# Oscilloscope.net
KiCad netlist of a schematic drawn in EasyEDA
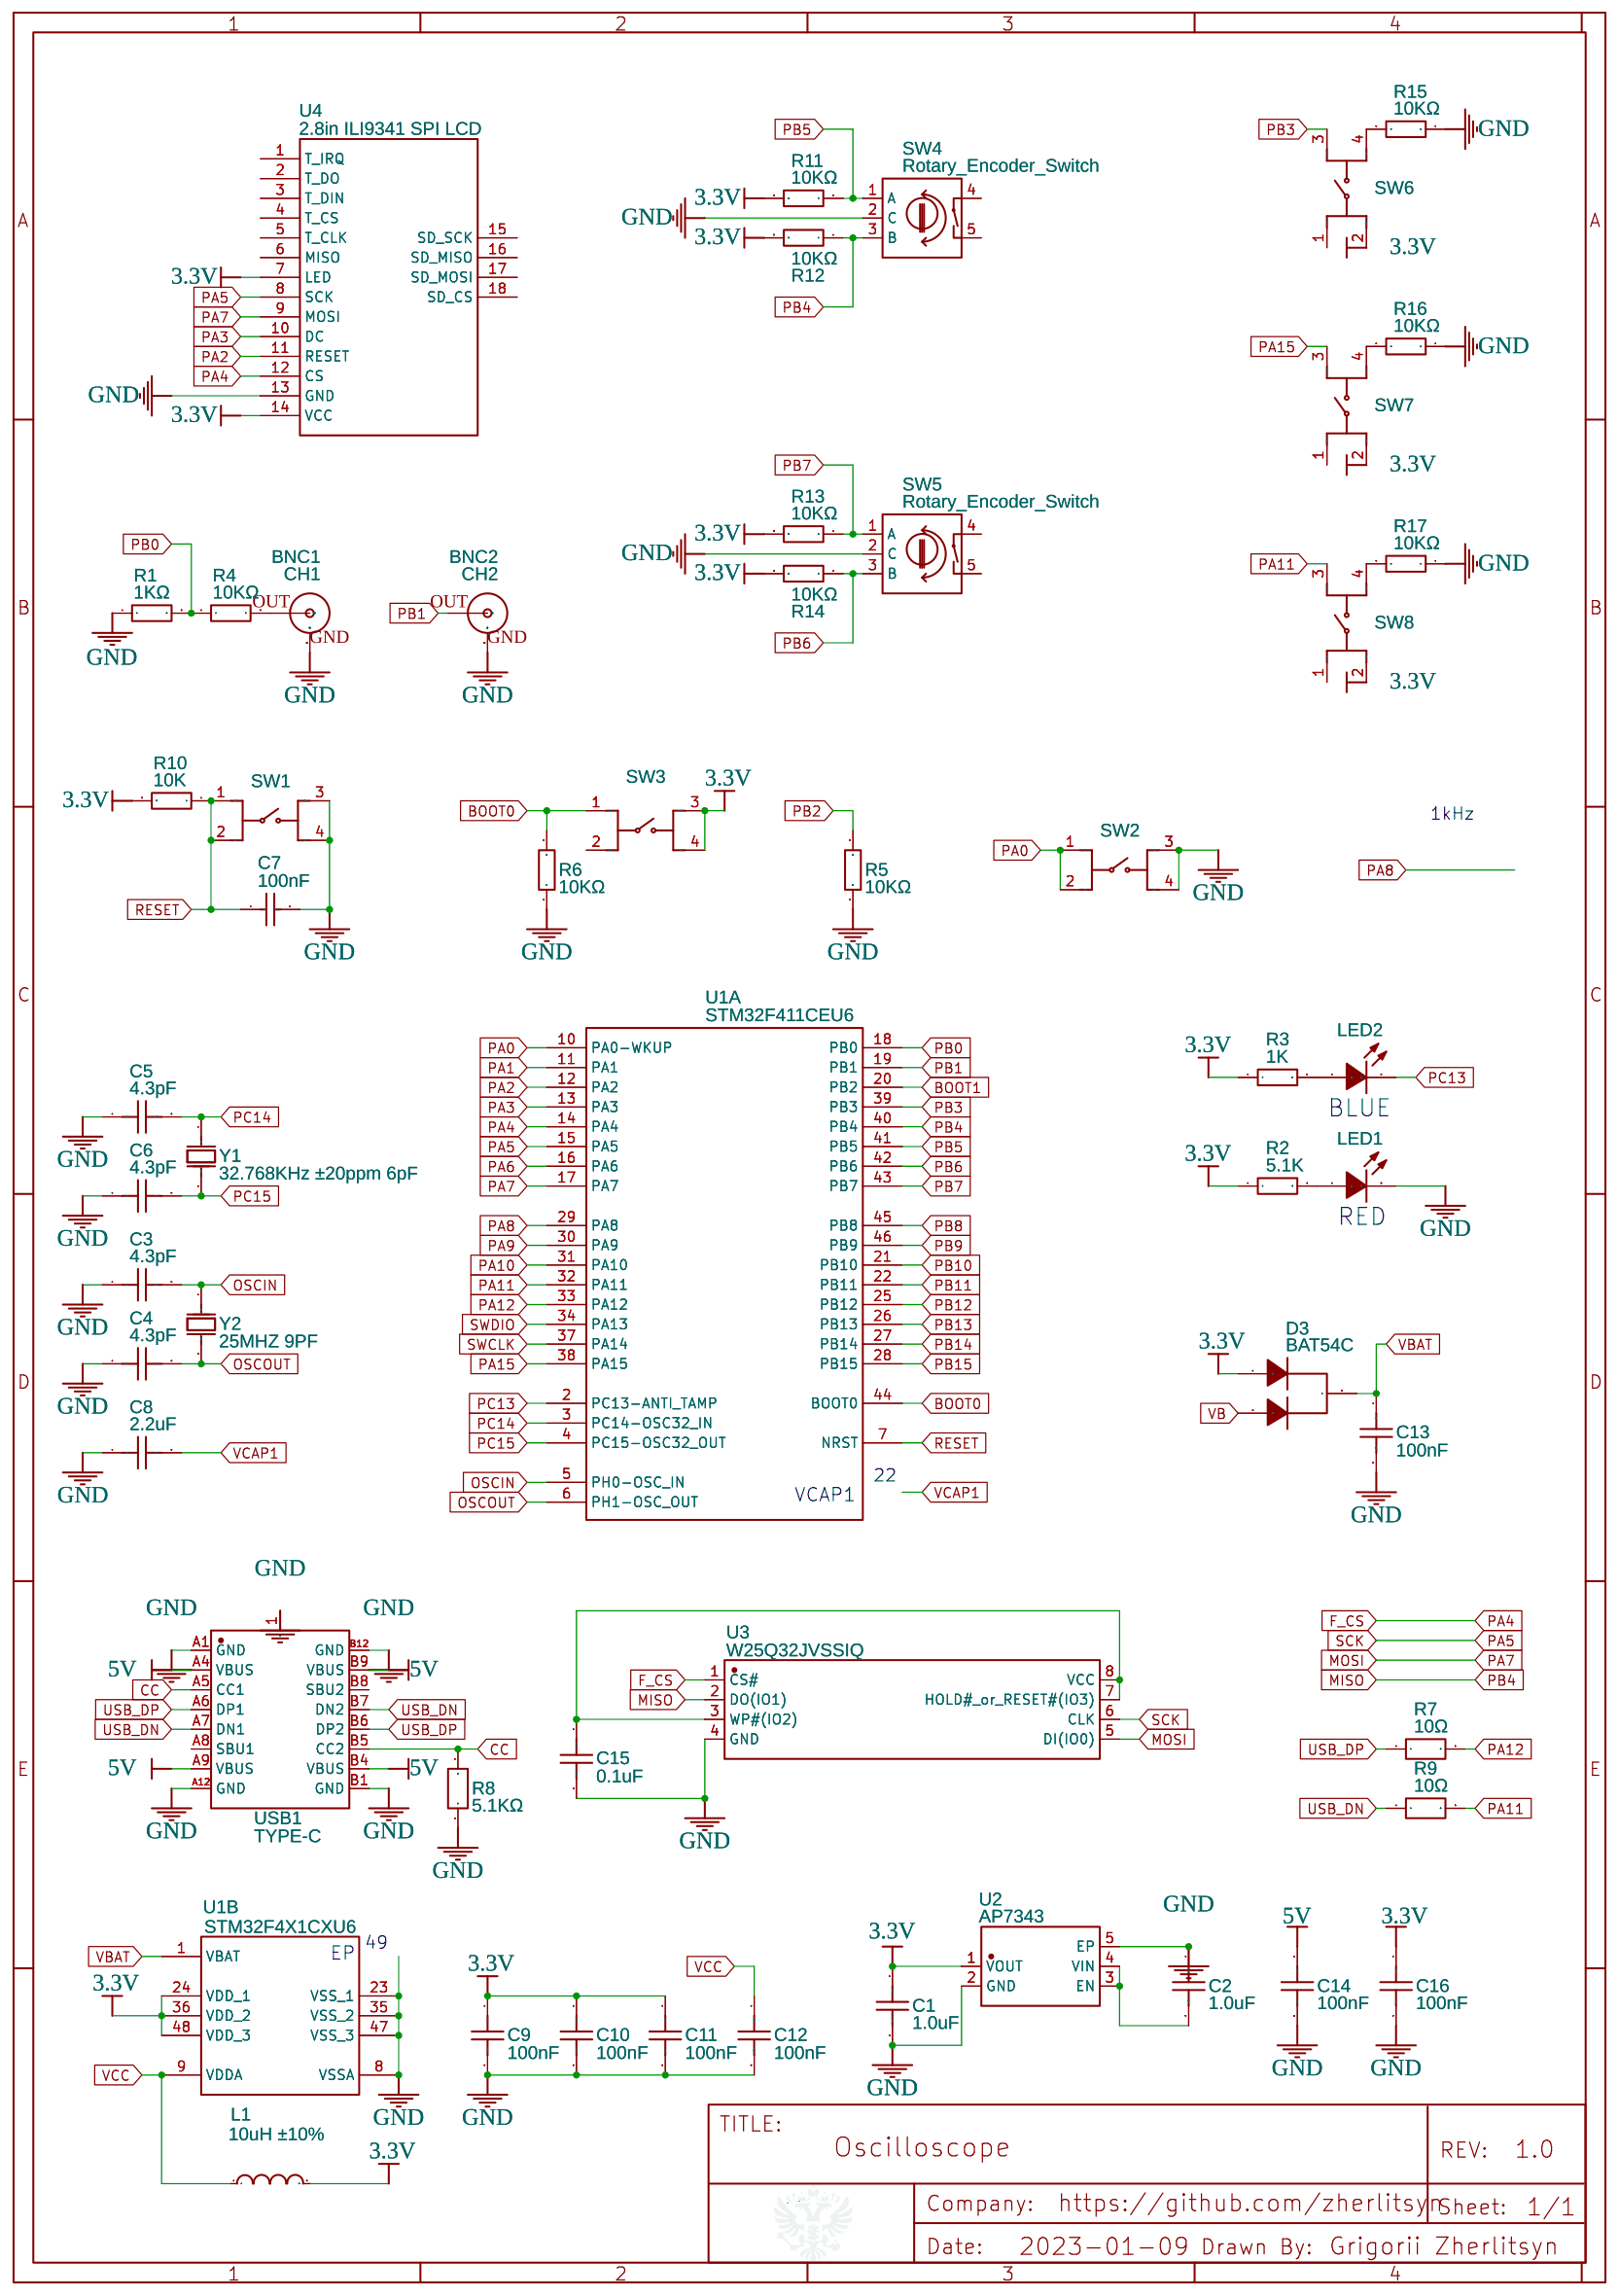
[diagram p0: schematic sheet]

(export (version "E")
  (design (tool "Eeschema 10.0.6"))
  (components
    (comp (ref "BNC1") (value "CH1") (libsource (lib "") (part "BNC")))
    (comp (ref "BNC2") (value "CH2") (libsource (lib "") (part "BNC")))
    (comp (ref "C1") (value "1.0uF") (libsource (lib "") (part "C_0603_US")))
    (comp (ref "C2") (value "1.0uF") (libsource (lib "") (part "C_0603_US")))
    (comp (ref "C3") (value "4.3pF") (libsource (lib "") (part "C_0603_US_1")))
    (comp (ref "C4") (value "4.3pF") (libsource (lib "") (part "C_0603_US_1")))
    (comp (ref "C5") (value "4.3pF") (libsource (lib "") (part "C_0603_US_1")))
    (comp (ref "C6") (value "4.3pF") (libsource (lib "") (part "C_0603_US_1")))
    (comp (ref "C7")
      (value "100nF")
      (fields (field (name "Manufacturer Part") "CL10A105KO8NNNC") (field (name "Manufacturer") "SAMSUNG"))
      (libsource (lib "") (part "CL10A105KO8NNNC"))
    )
    (comp (ref "C8") (value "2.2uF") (libsource (lib "") (part "C_0603_US_1")))
    (comp (ref "C9") (value "100nF") (libsource (lib "") (part "C_0603_US")))
    (comp (ref "C10") (value "100nF") (libsource (lib "") (part "C_0603_US")))
    (comp (ref "C11") (value "100nF") (libsource (lib "") (part "C_0603_US")))
    (comp (ref "C12") (value "100nF") (libsource (lib "") (part "C_0603_US")))
    (comp (ref "C13") (value "100nF") (libsource (lib "") (part "C_0603_US")))
    (comp (ref "C14") (value "100nF") (libsource (lib "") (part "C_0603_US")))
    (comp (ref "C15") (value "0.1uF") (libsource (lib "") (part "C_0603_US")))
    (comp (ref "C16") (value "100nF") (libsource (lib "") (part "C_0603_US")))
    (comp (ref "D3")
      (value "BAT54C")
      (fields (field (name "Manufacturer") "CJ(江苏长电/长晶)"))
      (libsource (lib "") (part "BAT54C"))
    )
    (comp (ref "L1") (value "10uH ±10%") (libsource (lib "") (part "L0603_US")))
    (comp (ref "LED1")
      (value "XL-0603QYGC")
      (fields (field (name "Manufacturer") "KENTO"))
      (libsource (lib "") (part "Unknown_680_-560"))
    )
    (comp (ref "LED2")
      (value "XL-0603QYGC")
      (fields (field (name "Manufacturer") "KENTO"))
      (libsource (lib "") (part "Unknown_680_-615"))
    )
    (comp (ref "R1")
      (value "1KΩ")
      (fields (field (name "Manufacturer Part") "RC0603FR-07510RL") (field (name "Manufacturer") "YAGEO"))
      (libsource (lib "") (part "RC0603FR-07510RL"))
    )
    (comp (ref "R2")
      (value "5.1K")
      (fields (field (name "Manufacturer Part") "RC0603FR-07510RL") (field (name "Manufacturer") "YAGEO"))
      (libsource (lib "") (part "RC0603FR-07510RL"))
    )
    (comp (ref "R3")
      (value "1K")
      (fields (field (name "Manufacturer Part") "RC0603FR-07510RL") (field (name "Manufacturer") "YAGEO"))
      (libsource (lib "") (part "RC0603FR-07510RL"))
    )
    (comp (ref "R4")
      (value "10KΩ")
      (fields (field (name "Manufacturer Part") "RC0603FR-07510RL") (field (name "Manufacturer") "YAGEO"))
      (libsource (lib "") (part "RC0603FR-07510RL"))
    )
    (comp (ref "R5")
      (value "10KΩ")
      (fields (field (name "Manufacturer Part") "RC0603FR-07510RL") (field (name "Manufacturer") "YAGEO"))
      (libsource (lib "") (part "RC0603FR-07510RL_2"))
    )
    (comp (ref "R6")
      (value "10KΩ")
      (fields (field (name "Manufacturer Part") "RC0603FR-07510RL") (field (name "Manufacturer") "YAGEO"))
      (libsource (lib "") (part "RC0603FR-07510RL_2"))
    )
    (comp (ref "R7") (value "10Ω") (libsource (lib "") (part "R_0603_EU_1")))
    (comp (ref "R8") (value "5.1KΩ") (libsource (lib "") (part "R_0603_EU")))
    (comp (ref "R9") (value "10Ω") (libsource (lib "") (part "R_0603_EU_1")))
    (comp (ref "R10")
      (value "10K")
      (fields (field (name "Manufacturer Part") "RC0603JR-0710KL") (field (name "Manufacturer") "YAGEO"))
      (libsource (lib "") (part "RC0603JR-0710KL"))
    )
    (comp (ref "R11")
      (value "10KΩ")
      (fields (field (name "Manufacturer Part") "RC0603FR-07510RL") (field (name "Manufacturer") "YAGEO"))
      (libsource (lib "") (part "RC0603FR-07510RL_1"))
    )
    (comp (ref "R12")
      (value "10KΩ")
      (fields (field (name "Manufacturer Part") "RC0603FR-07510RL") (field (name "Manufacturer") "YAGEO"))
      (libsource (lib "") (part "RC0603FR-07510RL_1"))
    )
    (comp (ref "R13")
      (value "10KΩ")
      (fields (field (name "Manufacturer Part") "RC0603FR-07510RL") (field (name "Manufacturer") "YAGEO"))
      (libsource (lib "") (part "RC0603FR-07510RL_1"))
    )
    (comp (ref "R14")
      (value "10KΩ")
      (fields (field (name "Manufacturer Part") "RC0603FR-07510RL") (field (name "Manufacturer") "YAGEO"))
      (libsource (lib "") (part "RC0603FR-07510RL_1"))
    )
    (comp (ref "R15")
      (value "10KΩ")
      (fields (field (name "Manufacturer Part") "RC0603FR-07510RL") (field (name "Manufacturer") "YAGEO"))
      (libsource (lib "") (part "RC0603FR-07510RL_1"))
    )
    (comp (ref "R16")
      (value "10KΩ")
      (fields (field (name "Manufacturer Part") "RC0603FR-07510RL") (field (name "Manufacturer") "YAGEO"))
      (libsource (lib "") (part "RC0603FR-07510RL_1"))
    )
    (comp (ref "R17")
      (value "10KΩ")
      (fields (field (name "Manufacturer Part") "RC0603FR-07510RL") (field (name "Manufacturer") "YAGEO"))
      (libsource (lib "") (part "RC0603FR-07510RL_1"))
    )
    (comp (ref "SW1")
      (value "K2-6639SP-C4SC-04")
      (fields (field (name "Manufacturer") "HRO"))
      (libsource (lib "") (part "Unknown_130_-745"))
    )
    (comp (ref "SW2")
      (value "K2-6639SP-C4SC-04")
      (fields (field (name "Manufacturer") "HRO"))
      (libsource (lib "") (part "Unknown_560_-720"))
    )
    (comp (ref "SW3")
      (value "K2-6639SP-C4SC-04")
      (fields (field (name "Manufacturer") "HRO"))
      (libsource (lib "") (part "Unknown_320_-740"))
    )
    (comp (ref "SW4") (value "Rotary_Encoder_Switch") (libsource (lib "") (part "Rotary_Encoder_Switch")))
    (comp (ref "SW5") (value "Rotary_Encoder_Switch") (libsource (lib "") (part "Rotary_Encoder_Switch")))
    (comp (ref "SW6")
      (value "K2-6639SP-C4SC-04")
      (fields (field (name "Manufacturer") "HRO"))
      (libsource (lib "") (part "Unknown_670_-1060"))
    )
    (comp (ref "SW7")
      (value "K2-6639SP-C4SC-04")
      (fields (field (name "Manufacturer") "HRO"))
      (libsource (lib "") (part "Unknown_670_-950"))
    )
    (comp (ref "SW8")
      (value "K2-6639SP-C4SC-04")
      (fields (field (name "Manufacturer") "HRO"))
      (libsource (lib "") (part "Unknown_670_-840"))
    )
    (comp (ref "U1A")
      (value "STM32F411CEU6")
      (fields (field (name "Manufacturer Part") "STM32F103C8T6") (field (name "Manufacturer") "ST"))
      (libsource (lib "") (part "Unknown_360_-510"))
    )
    (comp (ref "U1B")
      (value "STM32F4X1CXU6")
      (fields (field (name "Manufacturer Part") "STM32F103C8T6") (field (name "Manufacturer") "ST"))
      (libsource (lib "") (part "Unknown_135_-135"))
    )
    (comp (ref "U2")
      (value "AP7343")
      (fields
        (field (name "Manufacturer Part") "AP7343D-22FS4-7B")
        (field (name "Manufacturer") "DIODES(美台)")
      )
      (libsource (lib "") (part "AP7343D-22FS4-7B"))
    )
    (comp (ref "U3")
      (value "W25Q32JVSSIQ")
      (fields (field (name "Manufacturer") "WINBOND(华邦)"))
      (libsource (lib "") (part "W25Q32JVSSIQ_C179173"))
    )
    (comp (ref "U4") (value "2.8in ILI9341 SPI LCD") (libsource (lib "") (part "2.8in ILI9341 SPI LCD")))
    (comp (ref "USB1")
      (value "TYPE-C")
      (fields
        (field (name "Manufacturer Part") "TYPE-C-2.0-16PIN-SMT-3")
        (field (name "Manufacturer") "CIKI(皓富)")
      )
      (libsource (lib "") (part "TYPE-C-2.0-16PIN-SMT-3"))
    )
    (comp (ref "Y1")
      (value "32.768KHz ±20ppm 6pF")
      (fields (field (name "Manufacturer Part") "X49SD8MSD2SC") (field (name "Manufacturer") "YXC"))
      (libsource (lib "") (part "X49SD8MSD2SC"))
    )
    (comp (ref "Y2")
      (value "25MHZ 9PF")
      (fields (field (name "Manufacturer Part") "X49SD8MSD2SC") (field (name "Manufacturer") "YXC"))
      (libsource (lib "") (part "X49SD8MSD2SC"))
    )
  )
  (nets
    (net (code "1") (name "3.3V") (class "Default")
      (node (ref "C1") (pin "1") (pinfunction "1_1") (pintype "unspecified"))
      (node (ref "C10") (pin "1") (pinfunction "1_1") (pintype "unspecified"))
      (node (ref "C11") (pin "1") (pinfunction "1_1") (pintype "unspecified"))
      (node (ref "C16") (pin "1") (pinfunction "1_1") (pintype "unspecified"))
      (node (ref "C9") (pin "1") (pinfunction "1_1") (pintype "unspecified"))
      (node (ref "D3") (pin "1") (pinfunction "A1_1") (pintype "unspecified"))
      (node (ref "L1") (pin "2") (pinfunction "2_2") (pintype "unspecified"))
      (node (ref "R10") (pin "2") (pinfunction "2_2") (pintype "input"))
      (node (ref "R11") (pin "2") (pinfunction "2_2") (pintype "input"))
      (node (ref "R12") (pin "2") (pinfunction "2_2") (pintype "input"))
      (node (ref "R13") (pin "2") (pinfunction "2_2") (pintype "input"))
      (node (ref "R14") (pin "2") (pinfunction "2_2") (pintype "input"))
      (node (ref "R2") (pin "1") (pinfunction "1_1") (pintype "input"))
      (node (ref "R3") (pin "1") (pinfunction "1_1") (pintype "input"))
      (node (ref "SW3") (pin "3") (pinfunction "3_3") (pintype "unspecified"))
      (node (ref "SW3") (pin "4") (pinfunction "4_4") (pintype "unspecified"))
      (node (ref "SW6") (pin "2") (pinfunction "2_2") (pintype "unspecified"))
      (node (ref "SW7") (pin "2") (pinfunction "2_2") (pintype "unspecified"))
      (node (ref "SW8") (pin "2") (pinfunction "2_2") (pintype "unspecified"))
      (node (ref "U1B") (pin "24") (pinfunction "VDD_1_24") (pintype "passive"))
      (node (ref "U1B") (pin "36") (pinfunction "VDD_2_36") (pintype "passive"))
      (node (ref "U1B") (pin "48") (pinfunction "VDD_3_48") (pintype "passive"))
      (node (ref "U2") (pin "1") (pinfunction "VOUT_1") (pintype "unspecified"))
      (node (ref "U4") (pin "14") (pinfunction "VCC_14") (pintype "unspecified"))
      (node (ref "U4") (pin "7") (pinfunction "LED_7") (pintype "unspecified"))
    )
    (net (code "2") (name "5V") (class "Default")
      (node (ref "C14") (pin "1") (pinfunction "1_1") (pintype "unspecified"))
      (node (ref "USB1") (pin "A4") (pinfunction "VBUS_A4") (pintype "unspecified"))
      (node (ref "USB1") (pin "A9") (pinfunction "VBUS_A9") (pintype "unspecified"))
      (node (ref "USB1") (pin "B4") (pinfunction "VBUS_B4") (pintype "unspecified"))
      (node (ref "USB1") (pin "B9") (pinfunction "VBUS_B9") (pintype "unspecified"))
    )
    (net (code "3") (name "BOOT0") (class "Default")
      (node (ref "R6") (pin "2") (pinfunction "2_2") (pintype "input"))
      (node (ref "SW3") (pin "1") (pinfunction "1_1") (pintype "unspecified"))
      (node (ref "U1A") (pin "44") (pinfunction "BOOT0_44") (pintype "unspecified"))
    )
    (net (code "4") (name "BOOT1") (class "Default")
      (node (ref "U1A") (pin "20") (pinfunction "PB2_20") (pintype "bidirectional"))
    )
    (net (code "5") (name "CC") (class "Default")
      (node (ref "R8") (pin "1") (pinfunction "1_1") (pintype "unspecified"))
      (node (ref "USB1") (pin "A5") (pinfunction "CC1_A5") (pintype "unspecified"))
      (node (ref "USB1") (pin "B5") (pinfunction "CC2_B5") (pintype "unspecified"))
    )
    (net (code "6") (name "F_CS") (class "Default")
      (node (ref "U1A") (pin "14") (pinfunction "PA4_14") (pintype "bidirectional"))
      (node (ref "U3") (pin "1") (pinfunction "CS#_1") (pintype "unspecified"))
      (node (ref "U4") (pin "12") (pinfunction "CS_12") (pintype "unspecified"))
    )
    (net (code "7") (name "GND") (class "Default")
      (node (ref "BNC1") (pin "GND") (pinfunction "GND_GND") (pintype "unspecified"))
      (node (ref "BNC2") (pin "GND") (pinfunction "GND_GND") (pintype "unspecified"))
      (node (ref "C1") (pin "2") (pinfunction "2_2") (pintype "unspecified"))
      (node (ref "C10") (pin "2") (pinfunction "2_2") (pintype "unspecified"))
      (node (ref "C11") (pin "2") (pinfunction "2_2") (pintype "unspecified"))
      (node (ref "C12") (pin "2") (pinfunction "2_2") (pintype "unspecified"))
      (node (ref "C13") (pin "2") (pinfunction "2_2") (pintype "unspecified"))
      (node (ref "C14") (pin "2") (pinfunction "2_2") (pintype "unspecified"))
      (node (ref "C15") (pin "2") (pinfunction "2_2") (pintype "unspecified"))
      (node (ref "C16") (pin "2") (pinfunction "2_2") (pintype "unspecified"))
      (node (ref "C2") (pin "1") (pinfunction "1_1") (pintype "unspecified"))
      (node (ref "C3") (pin "1") (pinfunction "1_1") (pintype "unspecified"))
      (node (ref "C4") (pin "1") (pinfunction "1_1") (pintype "unspecified"))
      (node (ref "C5") (pin "1") (pinfunction "1_1") (pintype "unspecified"))
      (node (ref "C6") (pin "1") (pinfunction "1_1") (pintype "unspecified"))
      (node (ref "C7") (pin "2") (pinfunction "2_2") (pintype "input"))
      (node (ref "C8") (pin "1") (pinfunction "1_1") (pintype "unspecified"))
      (node (ref "C9") (pin "2") (pinfunction "2_2") (pintype "unspecified"))
      (node (ref "LED1") (pin "2") (pinfunction "K_2") (pintype "unspecified"))
      (node (ref "R1") (pin "1") (pinfunction "1_1") (pintype "input"))
      (node (ref "R15") (pin "1") (pinfunction "1_1") (pintype "input"))
      (node (ref "R16") (pin "1") (pinfunction "1_1") (pintype "input"))
      (node (ref "R17") (pin "1") (pinfunction "1_1") (pintype "input"))
      (node (ref "R5") (pin "1") (pinfunction "1_1") (pintype "input"))
      (node (ref "R6") (pin "1") (pinfunction "1_1") (pintype "input"))
      (node (ref "R8") (pin "2") (pinfunction "2_2") (pintype "unspecified"))
      (node (ref "SW1") (pin "3") (pinfunction "3_3") (pintype "unspecified"))
      (node (ref "SW1") (pin "4") (pinfunction "4_4") (pintype "unspecified"))
      (node (ref "SW2") (pin "3") (pinfunction "3_3") (pintype "unspecified"))
      (node (ref "SW2") (pin "4") (pinfunction "4_4") (pintype "unspecified"))
      (node (ref "SW4") (pin "2") (pinfunction "C_2") (pintype "input"))
      (node (ref "SW5") (pin "2") (pinfunction "C_2") (pintype "input"))
      (node (ref "U1B") (pin "23") (pinfunction "VSS_1_23") (pintype "passive"))
      (node (ref "U1B") (pin "35") (pinfunction "VSS_2_35") (pintype "passive"))
      (node (ref "U1B") (pin "47") (pinfunction "VSS_3_47") (pintype "passive"))
      (node (ref "U1B") (pin "8") (pinfunction "VSSA_8") (pintype "passive"))
      (node (ref "U2") (pin "2") (pinfunction "GND_2") (pintype "unspecified"))
      (node (ref "U2") (pin "5") (pinfunction "EP_5") (pintype "unspecified"))
      (node (ref "U3") (pin "4") (pinfunction "GND_4") (pintype "unspecified"))
      (node (ref "U4") (pin "13") (pinfunction "GND_13") (pintype "unspecified"))
      (node (ref "USB1") (pin "1") (pinfunction "EH_1") (pintype "unspecified"))
      (node (ref "USB1") (pin "A1") (pinfunction "GND_A1") (pintype "unspecified"))
      (node (ref "USB1") (pin "A12") (pinfunction "GND_A12") (pintype "unspecified"))
      (node (ref "USB1") (pin "B1") (pinfunction "GND_B1") (pintype "unspecified"))
      (node (ref "USB1") (pin "B12") (pinfunction "GND_B12") (pintype "unspecified"))
    )
    (net (code "8") (name "MISO") (class "Default")
      (node (ref "R12") (pin "1") (pinfunction "1_1") (pintype "input"))
      (node (ref "SW4") (pin "3") (pinfunction "B_3") (pintype "input"))
      (node (ref "U1A") (pin "40") (pinfunction "PB4_40") (pintype "bidirectional"))
      (node (ref "U3") (pin "2") (pinfunction "DO(IO1)_2") (pintype "unspecified"))
    )
    (net (code "9") (name "MOSI") (class "Default")
      (node (ref "U1A") (pin "17") (pinfunction "PA7_17") (pintype "bidirectional"))
      (node (ref "U3") (pin "5") (pinfunction "DI(IO0)_5") (pintype "unspecified"))
      (node (ref "U4") (pin "9") (pinfunction "MOSI_9") (pintype "unspecified"))
    )
    (net (code "10") (name "Net-(BNC1-OUT)") (class "Default")
      (node (ref "BNC1") (pin "S") (pinfunction "OUT_S") (pintype "unspecified"))
      (node (ref "R4") (pin "2") (pinfunction "2_2") (pintype "input"))
    )
    (net (code "11") (name "Net-(LED1-A)") (class "Default")
      (node (ref "LED1") (pin "1") (pinfunction "A_1") (pintype "unspecified"))
      (node (ref "R2") (pin "2") (pinfunction "2_2") (pintype "input"))
    )
    (net (code "12") (name "Net-(LED2-A)") (class "Default")
      (node (ref "LED2") (pin "1") (pinfunction "A_1") (pintype "unspecified"))
      (node (ref "R3") (pin "2") (pinfunction "2_2") (pintype "input"))
    )
    (net (code "13") (name "Net-(R15-Pad2)") (class "Default")
      (node (ref "R15") (pin "2") (pinfunction "2_2") (pintype "input"))
      (node (ref "SW6") (pin "4") (pinfunction "4_4") (pintype "unspecified"))
    )
    (net (code "14") (name "Net-(R16-Pad2)") (class "Default")
      (node (ref "R16") (pin "2") (pinfunction "2_2") (pintype "input"))
      (node (ref "SW7") (pin "4") (pinfunction "4_4") (pintype "unspecified"))
    )
    (net (code "15") (name "Net-(R17-Pad2)") (class "Default")
      (node (ref "R17") (pin "2") (pinfunction "2_2") (pintype "input"))
      (node (ref "SW8") (pin "4") (pinfunction "4_4") (pintype "unspecified"))
    )
    (net (code "16") (name "Net-(U2-EN)") (class "Default")
      (node (ref "C2") (pin "2") (pinfunction "2_2") (pintype "unspecified"))
      (node (ref "U2") (pin "3") (pinfunction "EN_3") (pintype "unspecified"))
      (node (ref "U2") (pin "4") (pinfunction "VIN_4") (pintype "unspecified"))
    )
    (net (code "17") (name "Net-(U3-HOLD#_or_RESET#(IO3))") (class "Default")
      (node (ref "C15") (pin "1") (pinfunction "1_1") (pintype "unspecified"))
      (node (ref "U3") (pin "3") (pinfunction "WP#(IO2)_3") (pintype "unspecified"))
      (node (ref "U3") (pin "7") (pinfunction "HOLD#_or_RESET#(IO3)_7") (pintype "unspecified"))
      (node (ref "U3") (pin "8") (pinfunction "VCC_8") (pintype "unspecified"))
    )
    (net (code "18") (name "OSCIN") (class "Default")
      (node (ref "C3") (pin "2") (pinfunction "2_2") (pintype "unspecified"))
      (node (ref "U1A") (pin "5") (pinfunction "PH0-OSC_IN_5") (pintype "bidirectional"))
      (node (ref "Y2") (pin "1") (pinfunction "OSC1_1") (pintype "input"))
    )
    (net (code "19") (name "OSCOUT") (class "Default")
      (node (ref "C4") (pin "2") (pinfunction "2_2") (pintype "unspecified"))
      (node (ref "U1A") (pin "6") (pinfunction "PH1-OSC_OUT_6") (pintype "bidirectional"))
      (node (ref "Y2") (pin "2") (pinfunction "OSC2_2") (pintype "input"))
    )
    (net (code "20") (name "PA0") (class "Default")
      (node (ref "SW2") (pin "1") (pinfunction "1_1") (pintype "unspecified"))
      (node (ref "SW2") (pin "2") (pinfunction "2_2") (pintype "unspecified"))
      (node (ref "U1A") (pin "10") (pinfunction "PA0-WKUP_10") (pintype "bidirectional"))
    )
    (net (code "21") (name "PA1") (class "Default")
      (node (ref "U1A") (pin "11") (pinfunction "PA1_11") (pintype "bidirectional"))
    )
    (net (code "22") (name "PA2") (class "Default")
      (node (ref "U1A") (pin "12") (pinfunction "PA2_12") (pintype "bidirectional"))
      (node (ref "U4") (pin "11") (pinfunction "RESET_11") (pintype "unspecified"))
    )
    (net (code "23") (name "PA3") (class "Default")
      (node (ref "U1A") (pin "13") (pinfunction "PA3_13") (pintype "bidirectional"))
      (node (ref "U4") (pin "10") (pinfunction "DC_10") (pintype "unspecified"))
    )
    (net (code "24") (name "PA5") (class "Default")
      (node (ref "U1A") (pin "15") (pinfunction "PA5_15") (pintype "bidirectional"))
      (node (ref "U3") (pin "6") (pinfunction "CLK_6") (pintype "unspecified"))
      (node (ref "U4") (pin "8") (pinfunction "SCK_8") (pintype "unspecified"))
    )
    (net (code "25") (name "PA6") (class "Default")
      (node (ref "U1A") (pin "16") (pinfunction "PA6_16") (pintype "bidirectional"))
    )
    (net (code "26") (name "PA8") (class "Default")
      (node (ref "U1A") (pin "29") (pinfunction "PA8_29") (pintype "bidirectional"))
    )
    (net (code "27") (name "PA9") (class "Default")
      (node (ref "U1A") (pin "30") (pinfunction "PA9_30") (pintype "bidirectional"))
    )
    (net (code "28") (name "PA10") (class "Default")
      (node (ref "U1A") (pin "31") (pinfunction "PA10_31") (pintype "bidirectional"))
    )
    (net (code "29") (name "PA11") (class "Default")
      (node (ref "R9") (pin "2") (pinfunction "2_2") (pintype "unspecified"))
      (node (ref "SW8") (pin "3") (pinfunction "3_3") (pintype "unspecified"))
      (node (ref "U1A") (pin "32") (pinfunction "PA11_32") (pintype "bidirectional"))
    )
    (net (code "30") (name "PA12") (class "Default")
      (node (ref "R7") (pin "2") (pinfunction "2_2") (pintype "unspecified"))
      (node (ref "U1A") (pin "33") (pinfunction "PA12_33") (pintype "bidirectional"))
    )
    (net (code "31") (name "PA15") (class "Default")
      (node (ref "SW7") (pin "3") (pinfunction "3_3") (pintype "unspecified"))
      (node (ref "U1A") (pin "38") (pinfunction "PA15_38") (pintype "bidirectional"))
    )
    (net (code "32") (name "PB0") (class "Default")
      (node (ref "R1") (pin "2") (pinfunction "2_2") (pintype "input"))
      (node (ref "R4") (pin "1") (pinfunction "1_1") (pintype "input"))
      (node (ref "U1A") (pin "18") (pinfunction "PB0_18") (pintype "bidirectional"))
    )
    (net (code "33") (name "PB1") (class "Default")
      (node (ref "BNC2") (pin "S") (pinfunction "OUT_S") (pintype "unspecified"))
      (node (ref "U1A") (pin "19") (pinfunction "PB1_19") (pintype "bidirectional"))
    )
    (net (code "34") (name "PB2") (class "Default")
      (node (ref "R5") (pin "2") (pinfunction "2_2") (pintype "input"))
    )
    (net (code "35") (name "PB3") (class "Default")
      (node (ref "SW6") (pin "3") (pinfunction "3_3") (pintype "unspecified"))
      (node (ref "U1A") (pin "39") (pinfunction "PB3_39") (pintype "bidirectional"))
    )
    (net (code "36") (name "PB5") (class "Default")
      (node (ref "R11") (pin "1") (pinfunction "1_1") (pintype "input"))
      (node (ref "SW4") (pin "1") (pinfunction "A_1") (pintype "input"))
      (node (ref "U1A") (pin "41") (pinfunction "PB5_41") (pintype "bidirectional"))
    )
    (net (code "37") (name "PB6") (class "Default")
      (node (ref "R14") (pin "1") (pinfunction "1_1") (pintype "input"))
      (node (ref "SW5") (pin "3") (pinfunction "B_3") (pintype "input"))
      (node (ref "U1A") (pin "42") (pinfunction "PB6_42") (pintype "bidirectional"))
    )
    (net (code "38") (name "PB7") (class "Default")
      (node (ref "R13") (pin "1") (pinfunction "1_1") (pintype "input"))
      (node (ref "SW5") (pin "1") (pinfunction "A_1") (pintype "input"))
      (node (ref "U1A") (pin "43") (pinfunction "PB7_43") (pintype "bidirectional"))
    )
    (net (code "39") (name "PB8") (class "Default")
      (node (ref "U1A") (pin "45") (pinfunction "PB8_45") (pintype "bidirectional"))
    )
    (net (code "40") (name "PB9") (class "Default")
      (node (ref "U1A") (pin "46") (pinfunction "PB9_46") (pintype "bidirectional"))
    )
    (net (code "41") (name "PB10") (class "Default")
      (node (ref "U1A") (pin "21") (pinfunction "PB10_21") (pintype "bidirectional"))
    )
    (net (code "42") (name "PB11") (class "Default")
      (node (ref "U1A") (pin "22") (pinfunction "PB11_22") (pintype "bidirectional"))
    )
    (net (code "43") (name "PB12") (class "Default")
      (node (ref "U1A") (pin "25") (pinfunction "PB12_25") (pintype "bidirectional"))
    )
    (net (code "44") (name "PB13") (class "Default")
      (node (ref "U1A") (pin "26") (pinfunction "PB13_26") (pintype "bidirectional"))
    )
    (net (code "45") (name "PB14") (class "Default")
      (node (ref "U1A") (pin "27") (pinfunction "PB14_27") (pintype "bidirectional"))
    )
    (net (code "46") (name "PB15") (class "Default")
      (node (ref "U1A") (pin "28") (pinfunction "PB15_28") (pintype "bidirectional"))
    )
    (net (code "47") (name "PC13") (class "Default")
      (node (ref "LED2") (pin "2") (pinfunction "K_2") (pintype "unspecified"))
      (node (ref "U1A") (pin "2") (pinfunction "PC13-ANTI_TAMP_2") (pintype "bidirectional"))
    )
    (net (code "48") (name "PC14") (class "Default")
      (node (ref "C5") (pin "2") (pinfunction "2_2") (pintype "unspecified"))
      (node (ref "U1A") (pin "3") (pinfunction "PC14-OSC32_IN_3") (pintype "bidirectional"))
      (node (ref "Y1") (pin "1") (pinfunction "OSC1_1") (pintype "input"))
    )
    (net (code "49") (name "PC15") (class "Default")
      (node (ref "C6") (pin "2") (pinfunction "2_2") (pintype "unspecified"))
      (node (ref "U1A") (pin "4") (pinfunction "PC15-OSC32_OUT_4") (pintype "bidirectional"))
      (node (ref "Y1") (pin "2") (pinfunction "OSC2_2") (pintype "input"))
    )
    (net (code "50") (name "RESET") (class "Default")
      (node (ref "C7") (pin "1") (pinfunction "1_1") (pintype "input"))
      (node (ref "R10") (pin "1") (pinfunction "1_1") (pintype "input"))
      (node (ref "SW1") (pin "1") (pinfunction "1_1") (pintype "unspecified"))
      (node (ref "SW1") (pin "2") (pinfunction "2_2") (pintype "unspecified"))
      (node (ref "U1A") (pin "7") (pinfunction "NRST_7") (pintype "bidirectional"))
    )
    (net (code "51") (name "SWCLK") (class "Default")
      (node (ref "U1A") (pin "37") (pinfunction "PA14_37") (pintype "bidirectional"))
    )
    (net (code "52") (name "SWDIO") (class "Default")
      (node (ref "U1A") (pin "34") (pinfunction "PA13_34") (pintype "bidirectional"))
    )
    (net (code "53") (name "USB_DN") (class "Default")
      (node (ref "R9") (pin "1") (pinfunction "1_1") (pintype "unspecified"))
      (node (ref "USB1") (pin "A7") (pinfunction "DN1_A7") (pintype "unspecified"))
      (node (ref "USB1") (pin "B7") (pinfunction "DN2_B7") (pintype "unspecified"))
    )
    (net (code "54") (name "USB_DP") (class "Default")
      (node (ref "R7") (pin "1") (pinfunction "1_1") (pintype "unspecified"))
      (node (ref "USB1") (pin "A6") (pinfunction "DP1_A6") (pintype "unspecified"))
      (node (ref "USB1") (pin "B6") (pinfunction "DP2_B6") (pintype "unspecified"))
    )
    (net (code "55") (name "VB") (class "Default")
      (node (ref "D3") (pin "2") (pinfunction "A2_2") (pintype "unspecified"))
    )
    (net (code "56") (name "VBAT") (class "Default")
      (node (ref "C13") (pin "1") (pinfunction "1_1") (pintype "unspecified"))
      (node (ref "D3") (pin "3") (pinfunction "K_3") (pintype "unspecified"))
      (node (ref "U1B") (pin "1") (pinfunction "VBAT_1") (pintype "passive"))
    )
    (net (code "57") (name "VCAP1") (class "Default")
      (node (ref "C8") (pin "2") (pinfunction "2_2") (pintype "unspecified"))
    )
    (net (code "58") (name "VCC") (class "Default")
      (node (ref "C12") (pin "1") (pinfunction "1_1") (pintype "unspecified"))
      (node (ref "L1") (pin "1") (pinfunction "1_1") (pintype "unspecified"))
      (node (ref "U1B") (pin "9") (pinfunction "VDDA_9") (pintype "passive"))
    )
    (net (code "59") (name "unconnected-(SW3-Pad2)") (class "Default")
      (node (ref "SW3") (pin "2") (pinfunction "2_2") (pintype "unspecified"))
    )
    (net (code "60") (name "unconnected-(SW4-Pad4)") (class "Default")
      (node (ref "SW4") (pin "4") (pintype "input"))
    )
    (net (code "61") (name "unconnected-(SW4-Pad5)") (class "Default")
      (node (ref "SW4") (pin "5") (pintype "input"))
    )
    (net (code "62") (name "unconnected-(SW5-Pad4)") (class "Default")
      (node (ref "SW5") (pin "4") (pintype "input"))
    )
    (net (code "63") (name "unconnected-(SW5-Pad5)") (class "Default")
      (node (ref "SW5") (pin "5") (pintype "input"))
    )
    (net (code "64") (name "unconnected-(SW6-Pad1)") (class "Default")
      (node (ref "SW6") (pin "1") (pinfunction "1_1") (pintype "unspecified"))
    )
    (net (code "65") (name "unconnected-(SW7-Pad1)") (class "Default")
      (node (ref "SW7") (pin "1") (pinfunction "1_1") (pintype "unspecified"))
    )
    (net (code "66") (name "unconnected-(SW8-Pad1)") (class "Default")
      (node (ref "SW8") (pin "1") (pinfunction "1_1") (pintype "unspecified"))
    )
    (net (code "67") (name "unconnected-(U4-MISO-Pad6)") (class "Default")
      (node (ref "U4") (pin "6") (pinfunction "MISO_6") (pintype "unspecified"))
    )
    (net (code "68") (name "unconnected-(U4-SD_CS-Pad18)") (class "Default")
      (node (ref "U4") (pin "18") (pinfunction "SD_CS_18") (pintype "unspecified"))
    )
    (net (code "69") (name "unconnected-(U4-SD_MISO-Pad16)") (class "Default")
      (node (ref "U4") (pin "16") (pinfunction "SD_MISO_16") (pintype "unspecified"))
    )
    (net (code "70") (name "unconnected-(U4-SD_MOSI-Pad17)") (class "Default")
      (node (ref "U4") (pin "17") (pinfunction "SD_MOSI_17") (pintype "unspecified"))
    )
    (net (code "71") (name "unconnected-(U4-SD_SCK-Pad15)") (class "Default")
      (node (ref "U4") (pin "15") (pinfunction "SD_SCK_15") (pintype "unspecified"))
    )
    (net (code "72") (name "unconnected-(U4-T_CLK-Pad5)") (class "Default")
      (node (ref "U4") (pin "5") (pinfunction "T_CLK_5") (pintype "unspecified"))
    )
    (net (code "73") (name "unconnected-(U4-T_CS-Pad4)") (class "Default")
      (node (ref "U4") (pin "4") (pinfunction "T_CS_4") (pintype "unspecified"))
    )
    (net (code "74") (name "unconnected-(U4-T_DIN-Pad3)") (class "Default")
      (node (ref "U4") (pin "3") (pinfunction "T_DIN_3") (pintype "unspecified"))
    )
    (net (code "75") (name "unconnected-(U4-T_DO-Pad2)") (class "Default")
      (node (ref "U4") (pin "2") (pinfunction "T_DO_2") (pintype "unspecified"))
    )
    (net (code "76") (name "unconnected-(U4-T_IRQ-Pad1)") (class "Default")
      (node (ref "U4") (pin "1") (pinfunction "T_IRQ_1") (pintype "unspecified"))
    )
    (net (code "77") (name "unconnected-(USB1-SBU1-PadA8)") (class "Default")
      (node (ref "USB1") (pin "A8") (pinfunction "SBU1_A8") (pintype "unspecified"))
    )
    (net (code "78") (name "unconnected-(USB1-SBU2-PadB8)") (class "Default")
      (node (ref "USB1") (pin "B8") (pinfunction "SBU2_B8") (pintype "unspecified"))
    )
  )
)
